# DIOBoard1.net
KiCad netlist of a schematic drawn in Altium Designer
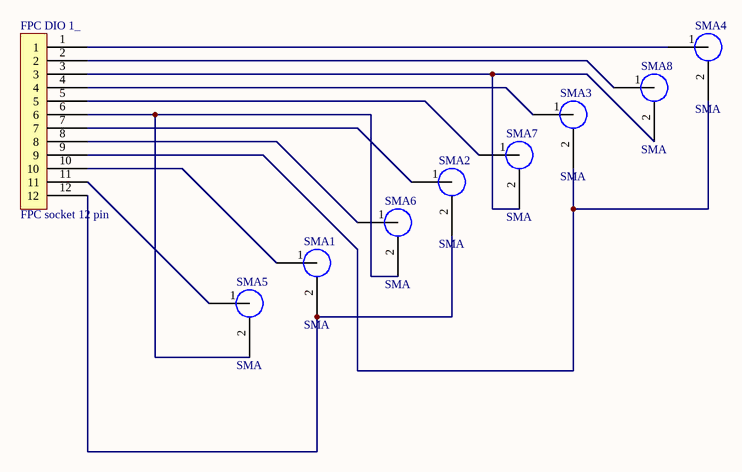
[diagram p0: DIOBoard1.SchDoc]

(export (version "E")
  (design (tool "Eeschema 10.0.6"))
  (components
    (comp (ref "FPC DIO 1_")
      (value "FPC socket 12 pin")
      (footprint "FPC 12pin")
      (libsource (lib "Libaray") (part "FPC socket 12 pin"))
    )
    (comp (ref "SMA1") (value "SMA") (footprint "SMA") (libsource (lib "Libaray") (part "SMA")))
    (comp (ref "SMA2") (value "SMA") (footprint "SMA") (libsource (lib "Libaray") (part "SMA")))
    (comp (ref "SMA3") (value "SMA") (footprint "SMA") (libsource (lib "Libaray") (part "SMA")))
    (comp (ref "SMA4") (value "SMA") (footprint "SMA") (libsource (lib "Libaray") (part "SMA")))
    (comp (ref "SMA5") (value "SMA") (footprint "SMA") (libsource (lib "Libaray") (part "SMA")))
    (comp (ref "SMA6") (value "SMA") (footprint "SMA") (libsource (lib "Libaray") (part "SMA")))
    (comp (ref "SMA7") (value "SMA") (footprint "SMA") (libsource (lib "Libaray") (part "SMA")))
    (comp (ref "SMA8") (value "SMA") (footprint "SMA") (libsource (lib "Libaray") (part "SMA")))
  )
  (nets
    (net (code "1") (name "Net-(SMA1-Core)") (class "Default")
      (node (ref "FPC DIO 1_") (pin "10") (pinfunction "10_10") (pintype "passive"))
      (node (ref "SMA1") (pin "1") (pinfunction "Core_1") (pintype "passive"))
    )
    (net (code "2") (name "Net-(SMA1-Ground)") (class "Default")
      (node (ref "FPC DIO 1_") (pin "12") (pinfunction "12_12") (pintype "passive"))
      (node (ref "SMA1") (pin "2") (pinfunction "Ground_2") (pintype "passive"))
      (node (ref "SMA2") (pin "2") (pinfunction "Ground_2") (pintype "passive"))
    )
    (net (code "3") (name "Net-(SMA2-Core)") (class "Default")
      (node (ref "FPC DIO 1_") (pin "7") (pinfunction "7_7") (pintype "passive"))
      (node (ref "SMA2") (pin "1") (pinfunction "Core_1") (pintype "passive"))
    )
    (net (code "4") (name "Net-(SMA3-Core)") (class "Default")
      (node (ref "FPC DIO 1_") (pin "4") (pinfunction "4_4") (pintype "passive"))
      (node (ref "SMA3") (pin "1") (pinfunction "Core_1") (pintype "passive"))
    )
    (net (code "5") (name "Net-(SMA3-Ground)") (class "Default")
      (node (ref "FPC DIO 1_") (pin "9") (pinfunction "9_9") (pintype "passive"))
      (node (ref "SMA3") (pin "2") (pinfunction "Ground_2") (pintype "passive"))
      (node (ref "SMA4") (pin "2") (pinfunction "Ground_2") (pintype "passive"))
    )
    (net (code "6") (name "Net-(SMA4-Core)") (class "Default")
      (node (ref "FPC DIO 1_") (pin "1") (pinfunction "1_1") (pintype "passive"))
      (node (ref "SMA4") (pin "1") (pinfunction "Core_1") (pintype "passive"))
    )
    (net (code "7") (name "Net-(SMA5-Core)") (class "Default")
      (node (ref "FPC DIO 1_") (pin "11") (pinfunction "11_11") (pintype "passive"))
      (node (ref "SMA5") (pin "1") (pinfunction "Core_1") (pintype "passive"))
    )
    (net (code "8") (name "Net-(SMA5-Ground)") (class "Default")
      (node (ref "FPC DIO 1_") (pin "6") (pinfunction "6_6") (pintype "passive"))
      (node (ref "SMA5") (pin "2") (pinfunction "Ground_2") (pintype "passive"))
      (node (ref "SMA6") (pin "2") (pinfunction "Ground_2") (pintype "passive"))
    )
    (net (code "9") (name "Net-(SMA6-Core)") (class "Default")
      (node (ref "FPC DIO 1_") (pin "8") (pinfunction "8_8") (pintype "passive"))
      (node (ref "SMA6") (pin "1") (pinfunction "Core_1") (pintype "passive"))
    )
    (net (code "10") (name "Net-(SMA7-Core)") (class "Default")
      (node (ref "FPC DIO 1_") (pin "5") (pinfunction "5_5") (pintype "passive"))
      (node (ref "SMA7") (pin "1") (pinfunction "Core_1") (pintype "passive"))
    )
    (net (code "11") (name "Net-(SMA7-Ground)") (class "Default")
      (node (ref "FPC DIO 1_") (pin "3") (pinfunction "3_3") (pintype "passive"))
      (node (ref "SMA7") (pin "2") (pinfunction "Ground_2") (pintype "passive"))
      (node (ref "SMA8") (pin "2") (pinfunction "Ground_2") (pintype "passive"))
    )
    (net (code "12") (name "Net-(SMA8-Core)") (class "Default")
      (node (ref "FPC DIO 1_") (pin "2") (pinfunction "2_2") (pintype "passive"))
      (node (ref "SMA8") (pin "1") (pinfunction "Core_1") (pintype "passive"))
    )
  )
)
